# Sheet2.net
KiCad netlist of a schematic drawn in Altium Designer
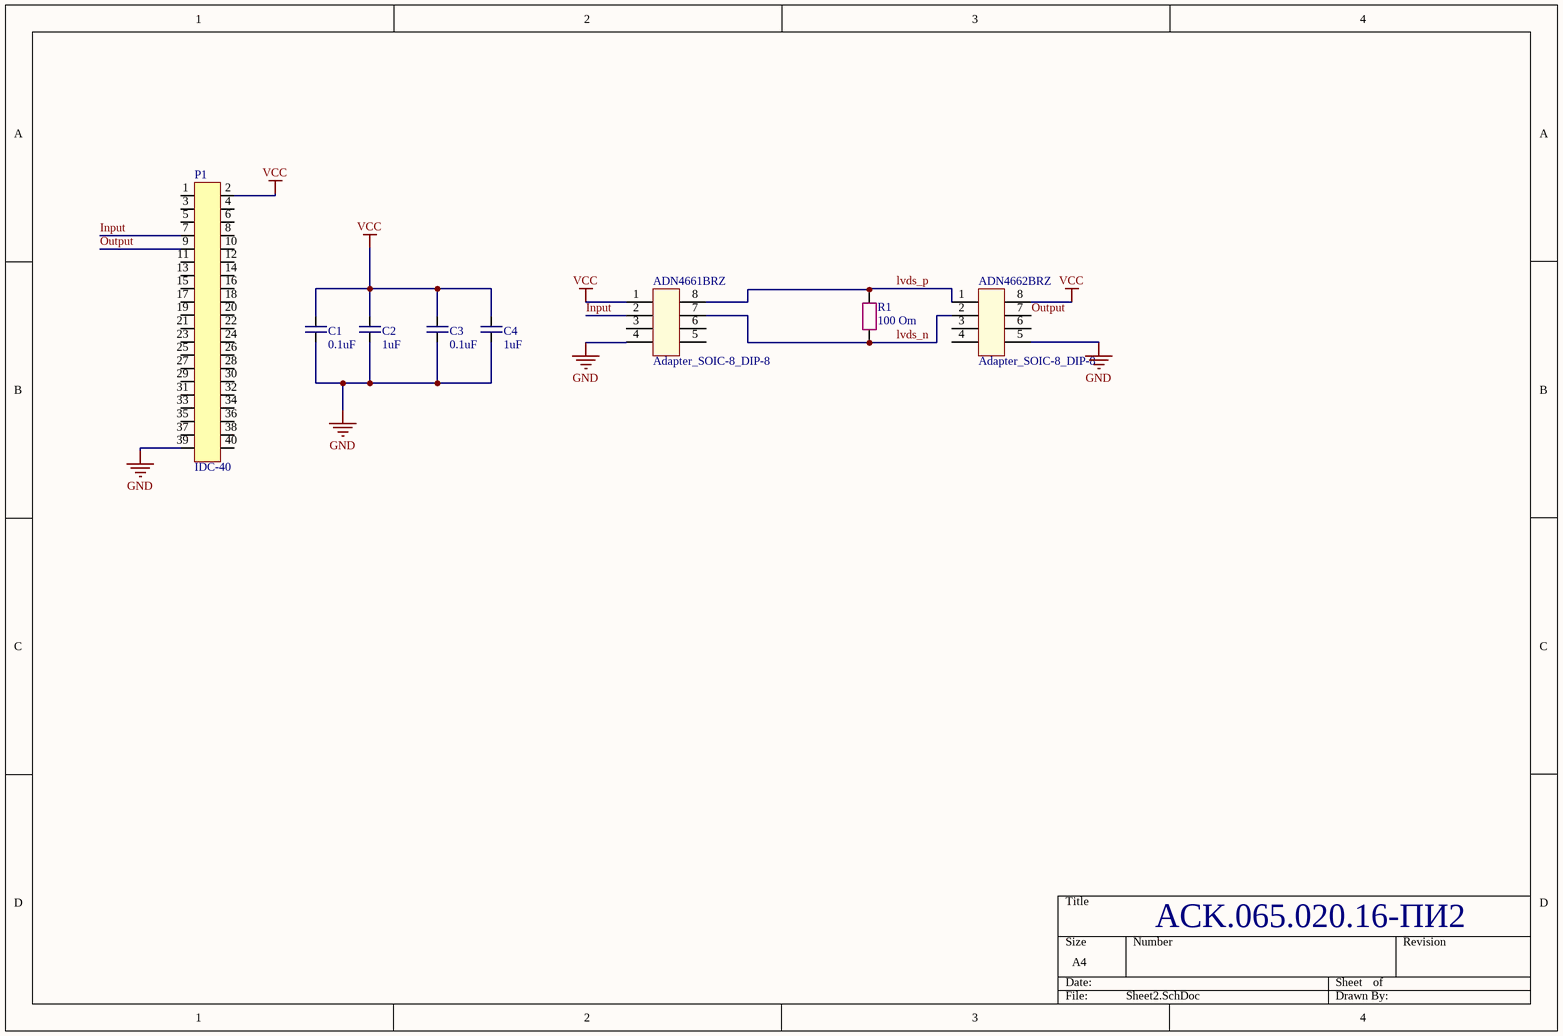
[diagram p0: Sheet2.SchDoc]

(export (version "E")
  (design (tool "Eeschema 10.0.6"))
  (components
    (comp (ref "ADN4661BRZ")
      (value "Adapter_SOIC-8_DIP-8")
      (footprint "Adapter_TSSOP-16_DIP-16_pins1-8")
      (libsource (lib "RCU") (part "Adapter_SOIC-8_DIP-8"))
    )
    (comp (ref "ADN4662BRZ")
      (value "Adapter_SOIC-8_DIP-8")
      (footprint "Adapter_TSSOP-16_DIP-16_pins1-8")
      (libsource (lib "RCU") (part "Adapter_SOIC-8_DIP-8"))
    )
    (comp (ref "C1") (value "0.1uF") (footprint "RCU:C_0805") (libsource (lib "RCU") (part "capacitor 0805")))
    (comp (ref "C2") (value "1uF") (footprint "RCU:C_0805") (libsource (lib "RCU") (part "capacitor 0805")))
    (comp (ref "C3") (value "0.1uF") (footprint "RCU:C_0805") (libsource (lib "RCU") (part "capacitor 0805")))
    (comp (ref "C4") (value "1uF") (footprint "RCU:C_0805") (libsource (lib "RCU") (part "capacitor 0805")))
    (comp (ref "P1")
      (value "IDC-40")
      (footprint "IDC-40")
      (description "разъем 2529")
      (libsource (lib "RCU") (part "IDC-40"))
    )
    (comp (ref "R1") (value "100 Om") (footprint "RCU:R_0805") (libsource (lib "RCU") (part "resistor 0805")))
  )
  (nets
    (net (code "1") (name "/Input") (class "Default")
      (node (ref "ADN4661BRZ") (pin "2") (pinfunction "36_2") (pintype "passive"))
      (node (ref "P1") (pin "7") (pinfunction "7_7") (pintype "passive"))
    )
    (net (code "2") (name "/Output") (class "Default")
      (node (ref "ADN4662BRZ") (pin "7") (pinfunction "41_7") (pintype "passive"))
      (node (ref "P1") (pin "9") (pinfunction "9_9") (pintype "passive"))
    )
    (net (code "3") (name "/lvds_n") (class "Default")
      (node (ref "ADN4661BRZ") (pin "7") (pinfunction "41_7") (pintype "passive"))
      (node (ref "ADN4662BRZ") (pin "2") (pinfunction "36_2") (pintype "passive"))
      (node (ref "R1") (pin "1") (pinfunction "1_1") (pintype "passive"))
    )
    (net (code "4") (name "/lvds_p") (class "Default")
      (node (ref "ADN4661BRZ") (pin "8") (pinfunction "42_8") (pintype "passive"))
      (node (ref "ADN4662BRZ") (pin "1") (pinfunction "35_1") (pintype "passive"))
      (node (ref "R1") (pin "2") (pinfunction "2_2") (pintype "passive"))
    )
    (net (code "5") (name "GND") (class "Default")
      (node (ref "ADN4661BRZ") (pin "4") (pinfunction "38_4") (pintype "passive"))
      (node (ref "ADN4662BRZ") (pin "5") (pinfunction "39_5") (pintype "passive"))
      (node (ref "C1") (pin "2") (pinfunction "2_2") (pintype "passive"))
      (node (ref "C2") (pin "2") (pinfunction "2_2") (pintype "passive"))
      (node (ref "C3") (pin "2") (pinfunction "2_2") (pintype "passive"))
      (node (ref "C4") (pin "2") (pinfunction "2_2") (pintype "passive"))
      (node (ref "P1") (pin "39") (pinfunction "39_39") (pintype "passive"))
    )
    (net (code "6") (name "VCC") (class "Default")
      (node (ref "ADN4661BRZ") (pin "1") (pinfunction "35_1") (pintype "passive"))
      (node (ref "ADN4662BRZ") (pin "8") (pinfunction "42_8") (pintype "passive"))
      (node (ref "C1") (pin "1") (pinfunction "1_1") (pintype "passive"))
      (node (ref "C2") (pin "1") (pinfunction "1_1") (pintype "passive"))
      (node (ref "C3") (pin "1") (pinfunction "1_1") (pintype "passive"))
      (node (ref "C4") (pin "1") (pinfunction "1_1") (pintype "passive"))
      (node (ref "P1") (pin "2") (pinfunction "2_2") (pintype "passive"))
    )
    (net (code "7") (name "unconnected-(ADN4661BRZ-37-Pad3)") (class "Default")
      (node (ref "ADN4661BRZ") (pin "3") (pinfunction "37_3") (pintype "passive"))
    )
    (net (code "8") (name "unconnected-(ADN4661BRZ-39-Pad5)") (class "Default")
      (node (ref "ADN4661BRZ") (pin "5") (pinfunction "39_5") (pintype "passive"))
    )
    (net (code "9") (name "unconnected-(ADN4661BRZ-40-Pad6)") (class "Default")
      (node (ref "ADN4661BRZ") (pin "6") (pinfunction "40_6") (pintype "passive"))
    )
    (net (code "10") (name "unconnected-(ADN4662BRZ-37-Pad3)") (class "Default")
      (node (ref "ADN4662BRZ") (pin "3") (pinfunction "37_3") (pintype "passive"))
    )
    (net (code "11") (name "unconnected-(ADN4662BRZ-38-Pad4)") (class "Default")
      (node (ref "ADN4662BRZ") (pin "4") (pinfunction "38_4") (pintype "passive"))
    )
    (net (code "12") (name "unconnected-(ADN4662BRZ-40-Pad6)") (class "Default")
      (node (ref "ADN4662BRZ") (pin "6") (pinfunction "40_6") (pintype "passive"))
    )
    (net (code "13") (name "unconnected-(P1-0-Pad1)") (class "Default")
      (node (ref "P1") (pin "1") (pinfunction "0_1") (pintype "passive"))
    )
    (net (code "14") (name "unconnected-(P1-Pad3)") (class "Default")
      (node (ref "P1") (pin "3") (pinfunction "3_3") (pintype "passive"))
    )
    (net (code "15") (name "unconnected-(P1-Pad4)") (class "Default")
      (node (ref "P1") (pin "4") (pinfunction "4_4") (pintype "passive"))
    )
    (net (code "16") (name "unconnected-(P1-Pad5)") (class "Default")
      (node (ref "P1") (pin "5") (pinfunction "5_5") (pintype "passive"))
    )
    (net (code "17") (name "unconnected-(P1-Pad6)") (class "Default")
      (node (ref "P1") (pin "6") (pinfunction "6_6") (pintype "passive"))
    )
    (net (code "18") (name "unconnected-(P1-Pad8)") (class "Default")
      (node (ref "P1") (pin "8") (pinfunction "8_8") (pintype "passive"))
    )
    (net (code "19") (name "unconnected-(P1-Pad10)") (class "Default")
      (node (ref "P1") (pin "10") (pinfunction "10_10") (pintype "passive"))
    )
    (net (code "20") (name "unconnected-(P1-Pad11)") (class "Default")
      (node (ref "P1") (pin "11") (pinfunction "11_11") (pintype "passive"))
    )
    (net (code "21") (name "unconnected-(P1-Pad12)") (class "Default")
      (node (ref "P1") (pin "12") (pinfunction "12_12") (pintype "passive"))
    )
    (net (code "22") (name "unconnected-(P1-Pad13)") (class "Default")
      (node (ref "P1") (pin "13") (pinfunction "13_13") (pintype "passive"))
    )
    (net (code "23") (name "unconnected-(P1-Pad14)") (class "Default")
      (node (ref "P1") (pin "14") (pinfunction "14_14") (pintype "passive"))
    )
    (net (code "24") (name "unconnected-(P1-Pad15)") (class "Default")
      (node (ref "P1") (pin "15") (pinfunction "15_15") (pintype "passive"))
    )
    (net (code "25") (name "unconnected-(P1-Pad16)") (class "Default")
      (node (ref "P1") (pin "16") (pinfunction "16_16") (pintype "passive"))
    )
    (net (code "26") (name "unconnected-(P1-Pad17)") (class "Default")
      (node (ref "P1") (pin "17") (pinfunction "17_17") (pintype "passive"))
    )
    (net (code "27") (name "unconnected-(P1-Pad18)") (class "Default")
      (node (ref "P1") (pin "18") (pinfunction "18_18") (pintype "passive"))
    )
    (net (code "28") (name "unconnected-(P1-Pad19)") (class "Default")
      (node (ref "P1") (pin "19") (pinfunction "19_19") (pintype "passive"))
    )
    (net (code "29") (name "unconnected-(P1-Pad20)") (class "Default")
      (node (ref "P1") (pin "20") (pinfunction "20_20") (pintype "passive"))
    )
    (net (code "30") (name "unconnected-(P1-Pad21)") (class "Default")
      (node (ref "P1") (pin "21") (pinfunction "21_21") (pintype "passive"))
    )
    (net (code "31") (name "unconnected-(P1-Pad22)") (class "Default")
      (node (ref "P1") (pin "22") (pinfunction "22_22") (pintype "passive"))
    )
    (net (code "32") (name "unconnected-(P1-Pad23)") (class "Default")
      (node (ref "P1") (pin "23") (pinfunction "23_23") (pintype "passive"))
    )
    (net (code "33") (name "unconnected-(P1-Pad24)") (class "Default")
      (node (ref "P1") (pin "24") (pinfunction "24_24") (pintype "passive"))
    )
    (net (code "34") (name "unconnected-(P1-Pad25)") (class "Default")
      (node (ref "P1") (pin "25") (pinfunction "25_25") (pintype "passive"))
    )
    (net (code "35") (name "unconnected-(P1-Pad26)") (class "Default")
      (node (ref "P1") (pin "26") (pinfunction "26_26") (pintype "passive"))
    )
    (net (code "36") (name "unconnected-(P1-Pad27)") (class "Default")
      (node (ref "P1") (pin "27") (pinfunction "27_27") (pintype "passive"))
    )
    (net (code "37") (name "unconnected-(P1-Pad28)") (class "Default")
      (node (ref "P1") (pin "28") (pinfunction "28_28") (pintype "passive"))
    )
    (net (code "38") (name "unconnected-(P1-Pad29)") (class "Default")
      (node (ref "P1") (pin "29") (pinfunction "29_29") (pintype "passive"))
    )
    (net (code "39") (name "unconnected-(P1-Pad30)") (class "Default")
      (node (ref "P1") (pin "30") (pinfunction "30_30") (pintype "passive"))
    )
    (net (code "40") (name "unconnected-(P1-Pad31)") (class "Default")
      (node (ref "P1") (pin "31") (pinfunction "31_31") (pintype "passive"))
    )
    (net (code "41") (name "unconnected-(P1-Pad32)") (class "Default")
      (node (ref "P1") (pin "32") (pinfunction "32_32") (pintype "passive"))
    )
    (net (code "42") (name "unconnected-(P1-Pad33)") (class "Default")
      (node (ref "P1") (pin "33") (pinfunction "33_33") (pintype "passive"))
    )
    (net (code "43") (name "unconnected-(P1-Pad34)") (class "Default")
      (node (ref "P1") (pin "34") (pinfunction "34_34") (pintype "passive"))
    )
    (net (code "44") (name "unconnected-(P1-Pad35)") (class "Default")
      (node (ref "P1") (pin "35") (pinfunction "35_35") (pintype "passive"))
    )
    (net (code "45") (name "unconnected-(P1-Pad36)") (class "Default")
      (node (ref "P1") (pin "36") (pinfunction "36_36") (pintype "passive"))
    )
    (net (code "46") (name "unconnected-(P1-Pad37)") (class "Default")
      (node (ref "P1") (pin "37") (pinfunction "37_37") (pintype "passive"))
    )
    (net (code "47") (name "unconnected-(P1-Pad38)") (class "Default")
      (node (ref "P1") (pin "38") (pinfunction "38_38") (pintype "passive"))
    )
    (net (code "48") (name "unconnected-(P1-Pad40)") (class "Default")
      (node (ref "P1") (pin "40") (pinfunction "40_40") (pintype "passive"))
    )
  )
)
